# M503A.net
KiCad netlist of a schematic drawn in EAGLE
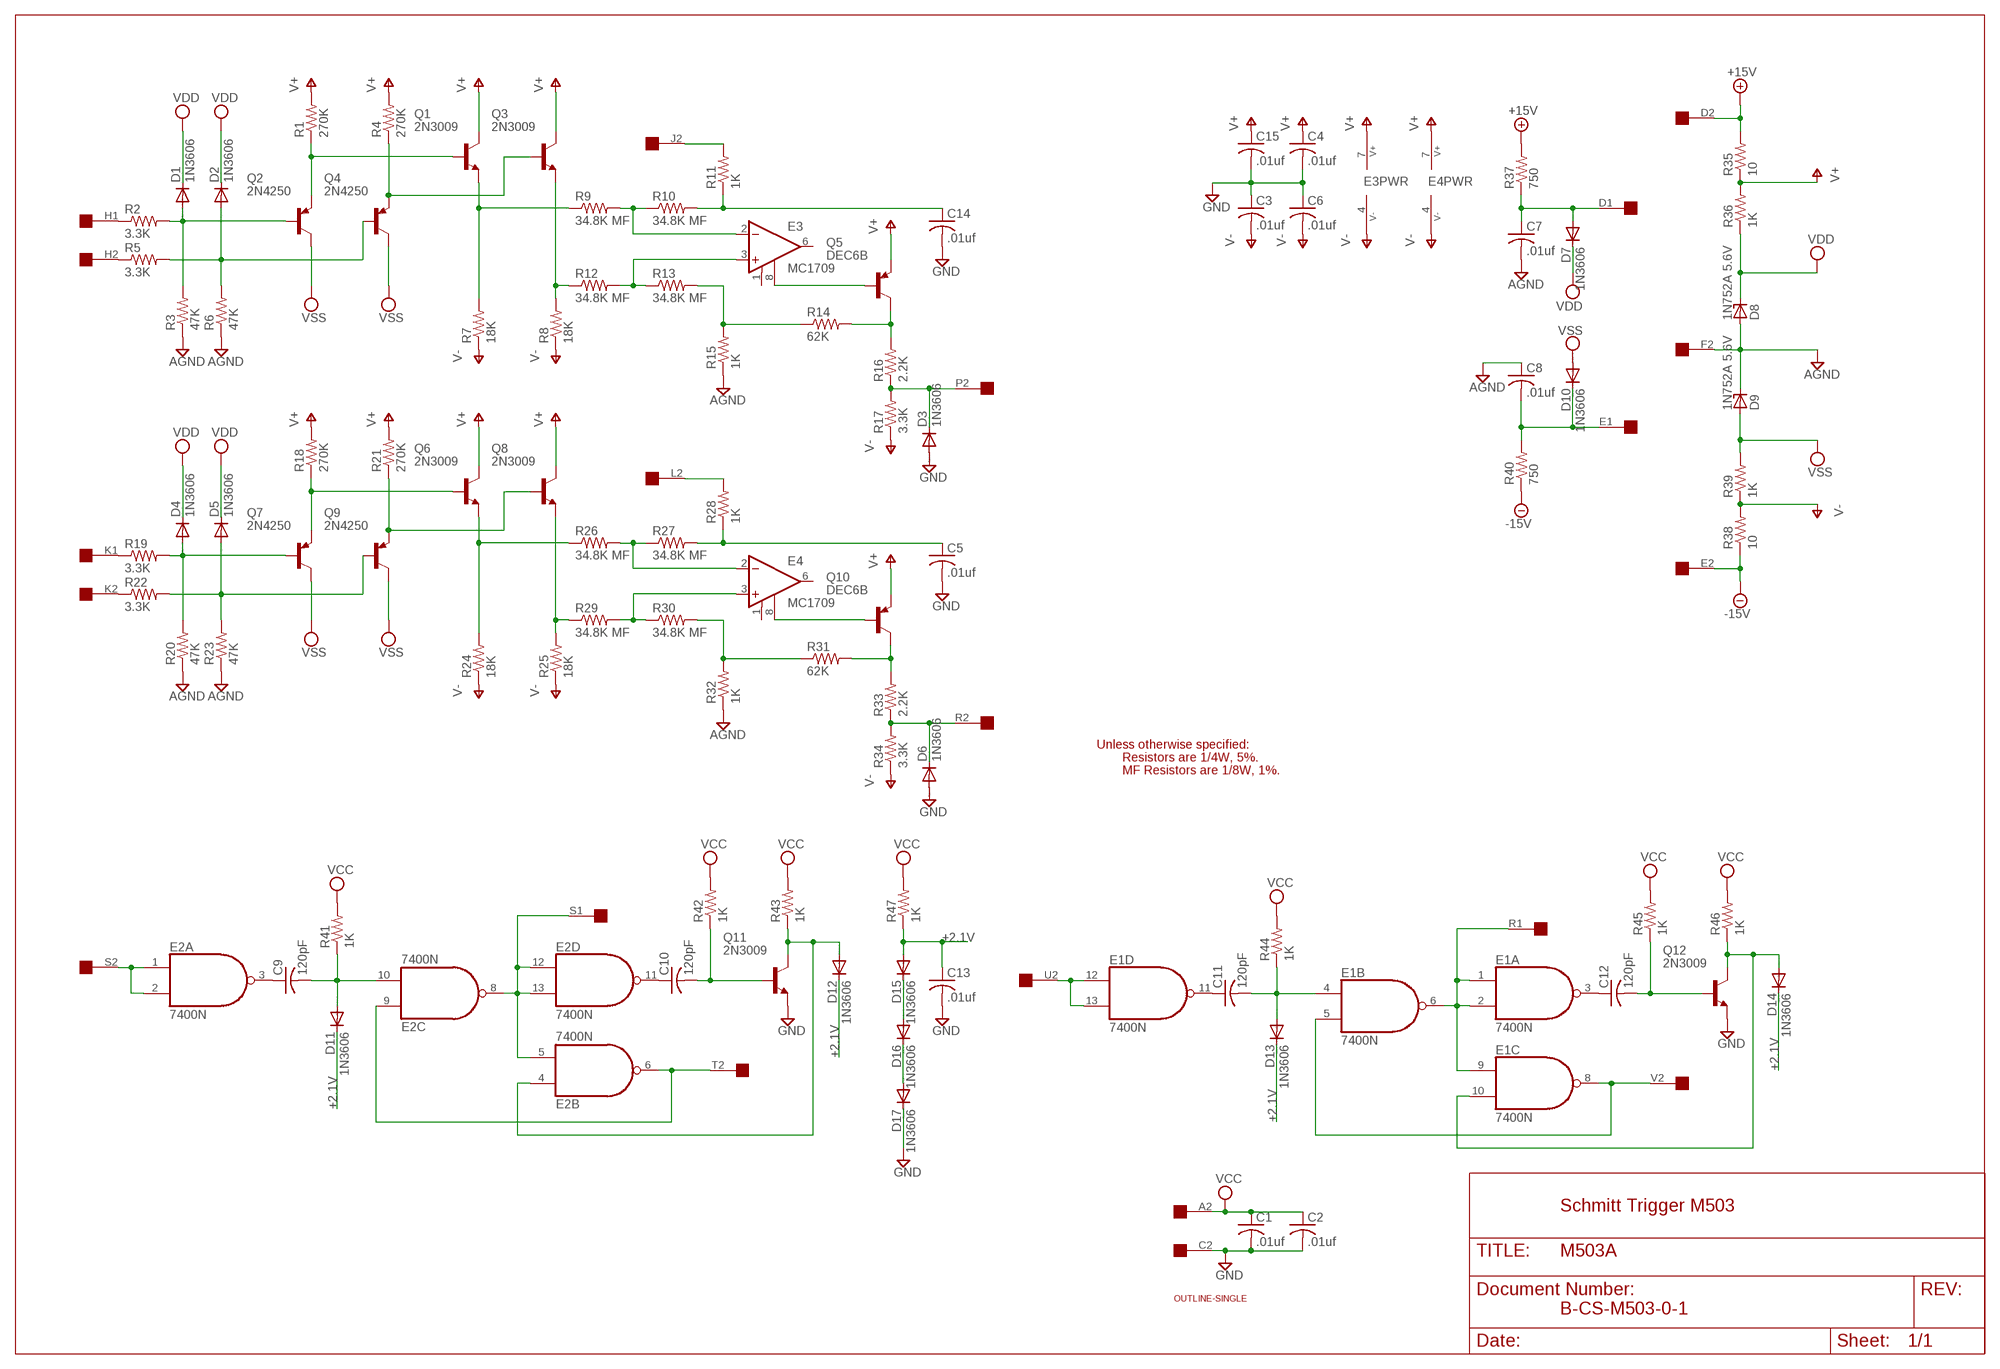
[diagram p0: schematic, sheet 1]

(export (version "E")
  (design (tool "Eeschema 10.0.6"))
  (components
    (comp (ref "C1")
      (value ".01uf")
      (footprint "eagle-import:C075-032X103")
      (libsource (lib "eagle-import") (part "C-US075-032X103"))
    )
    (comp (ref "C2")
      (value ".01uf")
      (footprint "eagle-import:C075-032X103")
      (libsource (lib "eagle-import") (part "C-US075-032X103"))
    )
    (comp (ref "C3")
      (value ".01uf")
      (footprint "eagle-import:C050-025X075")
      (libsource (lib "eagle-import") (part "C-US050-025X075"))
    )
    (comp (ref "C4")
      (value ".01uf")
      (footprint "eagle-import:C050-025X075")
      (libsource (lib "eagle-import") (part "C-US050-025X075"))
    )
    (comp (ref "C5")
      (value ".01uf")
      (footprint "eagle-import:C050-025X075")
      (libsource (lib "eagle-import") (part "C-US050-025X075"))
    )
    (comp (ref "C6")
      (value ".01uf")
      (footprint "eagle-import:C050-025X075")
      (libsource (lib "eagle-import") (part "C-US050-025X075"))
    )
    (comp (ref "C7")
      (value ".01uf")
      (footprint "eagle-import:C050-025X075")
      (libsource (lib "eagle-import") (part "C-US050-025X075"))
    )
    (comp (ref "C8")
      (value ".01uf")
      (footprint "eagle-import:C050-025X075")
      (libsource (lib "eagle-import") (part "C-US050-025X075"))
    )
    (comp (ref "C9")
      (value "120pF")
      (footprint "eagle-import:C050-025X075")
      (libsource (lib "eagle-import") (part "C-US050-025X075"))
    )
    (comp (ref "C10")
      (value "120pF")
      (footprint "eagle-import:C050-025X075")
      (libsource (lib "eagle-import") (part "C-US050-025X075"))
    )
    (comp (ref "C11")
      (value "120pF")
      (footprint "eagle-import:C050-025X075")
      (libsource (lib "eagle-import") (part "C-US050-025X075"))
    )
    (comp (ref "C12")
      (value "120pF")
      (footprint "eagle-import:C050-025X075")
      (libsource (lib "eagle-import") (part "C-US050-025X075"))
    )
    (comp (ref "C13")
      (value ".01uf")
      (footprint "eagle-import:C050-025X075")
      (libsource (lib "eagle-import") (part "C-US050-025X075"))
    )
    (comp (ref "C14")
      (value ".01uf")
      (footprint "eagle-import:C050-025X075")
      (libsource (lib "eagle-import") (part "C-US050-025X075"))
    )
    (comp (ref "C15")
      (value ".01uf")
      (footprint "eagle-import:C050-025X075")
      (libsource (lib "eagle-import") (part "C-US050-025X075"))
    )
    (comp (ref "D1")
      (value "1N3606")
      (footprint "eagle-import:DO35-10")
      (libsource (lib "eagle-import") (part "1N4148DO35-10"))
    )
    (comp (ref "D2")
      (value "1N3606")
      (footprint "eagle-import:DO35-10")
      (libsource (lib "eagle-import") (part "1N4148DO35-10"))
    )
    (comp (ref "D3")
      (value "1N3606")
      (footprint "eagle-import:DO35-10")
      (libsource (lib "eagle-import") (part "1N4148DO35-10"))
    )
    (comp (ref "D4")
      (value "1N3606")
      (footprint "eagle-import:DO35-10")
      (libsource (lib "eagle-import") (part "1N4148DO35-10"))
    )
    (comp (ref "D5")
      (value "1N3606")
      (footprint "eagle-import:DO35-10")
      (libsource (lib "eagle-import") (part "1N4148DO35-10"))
    )
    (comp (ref "D6")
      (value "1N3606")
      (footprint "eagle-import:DO35-10")
      (libsource (lib "eagle-import") (part "1N4148DO35-10"))
    )
    (comp (ref "D7")
      (value "1N3606")
      (footprint "eagle-import:DO35-10")
      (libsource (lib "eagle-import") (part "1N4148DO35-10"))
    )
    (comp (ref "D8")
      (value "1N752A 5.6V")
      (footprint "eagle-import:DO35Z10")
      (libsource (lib "eagle-import") (part "ZENER-DIODEDO35Z10"))
    )
    (comp (ref "D9")
      (value "1N752A 5.6V")
      (footprint "eagle-import:DO35Z10")
      (libsource (lib "eagle-import") (part "ZENER-DIODEDO35Z10"))
    )
    (comp (ref "D10")
      (value "1N3606")
      (footprint "eagle-import:DO35-10")
      (libsource (lib "eagle-import") (part "1N4148DO35-10"))
    )
    (comp (ref "D11")
      (value "1N3606")
      (footprint "eagle-import:DO35-10")
      (libsource (lib "eagle-import") (part "1N4148DO35-10"))
    )
    (comp (ref "D12")
      (value "1N3606")
      (footprint "eagle-import:DO35-10")
      (libsource (lib "eagle-import") (part "1N4148DO35-10"))
    )
    (comp (ref "D13")
      (value "1N3606")
      (footprint "eagle-import:DO35-10")
      (libsource (lib "eagle-import") (part "1N4148DO35-10"))
    )
    (comp (ref "D14")
      (value "1N3606")
      (footprint "eagle-import:DO35-10")
      (libsource (lib "eagle-import") (part "1N4148DO35-10"))
    )
    (comp (ref "D15")
      (value "1N3606")
      (footprint "eagle-import:DO35-10")
      (libsource (lib "eagle-import") (part "1N4148DO35-10"))
    )
    (comp (ref "D16")
      (value "1N3606")
      (footprint "eagle-import:DO35-10")
      (libsource (lib "eagle-import") (part "1N4148DO35-10"))
    )
    (comp (ref "D17")
      (value "1N3606")
      (footprint "eagle-import:DO35-10")
      (libsource (lib "eagle-import") (part "1N4148DO35-10"))
    )
    (comp (ref "E1")
      (value "7400N")
      (footprint "eagle-import:DIL14")
      (libsource (lib "eagle-import") (part "7400N"))
    )
    (comp (ref "E2")
      (value "7400N")
      (footprint "eagle-import:DIL14")
      (libsource (lib "eagle-import") (part "7400N"))
    )
    (comp (ref "E3")
      (value "MC1709")
      (footprint "eagle-import:TO99C")
      (libsource (lib "eagle-import") (part "LM301C"))
    )
    (comp (ref "E4")
      (value "MC1709")
      (footprint "eagle-import:TO99B")
      (libsource (lib "eagle-import") (part "LM301B"))
    )
    (comp (ref "Q1")
      (value "2N3009")
      (footprint "eagle-import:TO39")
      (libsource (lib "eagle-import") (part "2N3019"))
    )
    (comp (ref "Q2")
      (value "2N4250")
      (footprint "eagle-import:TO39")
      (libsource (lib "eagle-import") (part "2N2904"))
    )
    (comp (ref "Q3")
      (value "2N3009")
      (footprint "eagle-import:TO39")
      (libsource (lib "eagle-import") (part "2N3019"))
    )
    (comp (ref "Q4")
      (value "2N4250")
      (footprint "eagle-import:TO39")
      (libsource (lib "eagle-import") (part "2N2904"))
    )
    (comp (ref "Q5")
      (value "DEC6B")
      (footprint "eagle-import:TO39")
      (libsource (lib "eagle-import") (part "2N2904"))
    )
    (comp (ref "Q6")
      (value "2N3009")
      (footprint "eagle-import:TO39")
      (libsource (lib "eagle-import") (part "2N3019"))
    )
    (comp (ref "Q7")
      (value "2N4250")
      (footprint "eagle-import:TO39")
      (libsource (lib "eagle-import") (part "2N2904"))
    )
    (comp (ref "Q8")
      (value "2N3009")
      (footprint "eagle-import:TO39")
      (libsource (lib "eagle-import") (part "2N3019"))
    )
    (comp (ref "Q9")
      (value "2N4250")
      (footprint "eagle-import:TO39")
      (libsource (lib "eagle-import") (part "2N2904"))
    )
    (comp (ref "Q10")
      (value "DEC6B")
      (footprint "eagle-import:TO39")
      (libsource (lib "eagle-import") (part "2N2904"))
    )
    (comp (ref "Q11")
      (value "2N3009")
      (footprint "eagle-import:TO39")
      (libsource (lib "eagle-import") (part "2N3019"))
    )
    (comp (ref "Q12")
      (value "2N3009")
      (footprint "eagle-import:TO39")
      (libsource (lib "eagle-import") (part "2N3019"))
    )
    (comp (ref "R1")
      (value "270K")
      (footprint "eagle-import:0207_10")
      (libsource (lib "eagle-import") (part "R-US_0207/10"))
    )
    (comp (ref "R2")
      (value "3.3K")
      (footprint "eagle-import:0207_10")
      (libsource (lib "eagle-import") (part "R-US_0207/10"))
    )
    (comp (ref "R3")
      (value "47K")
      (footprint "eagle-import:0207_10")
      (libsource (lib "eagle-import") (part "R-US_0207/10"))
    )
    (comp (ref "R4")
      (value "270K")
      (footprint "eagle-import:0207_10")
      (libsource (lib "eagle-import") (part "R-US_0207/10"))
    )
    (comp (ref "R5")
      (value "3.3K")
      (footprint "eagle-import:0207_10")
      (libsource (lib "eagle-import") (part "R-US_0207/10"))
    )
    (comp (ref "R6")
      (value "47K")
      (footprint "eagle-import:0207_10")
      (libsource (lib "eagle-import") (part "R-US_0207/10"))
    )
    (comp (ref "R7")
      (value "18K")
      (footprint "eagle-import:0207_10")
      (libsource (lib "eagle-import") (part "R-US_0207/10"))
    )
    (comp (ref "R8")
      (value "18K")
      (footprint "eagle-import:0207_10")
      (libsource (lib "eagle-import") (part "R-US_0207/10"))
    )
    (comp (ref "R9")
      (value "34.8K MF")
      (footprint "eagle-import:0207_10")
      (libsource (lib "eagle-import") (part "R-US_0207/10"))
    )
    (comp (ref "R10")
      (value "34.8K MF")
      (footprint "eagle-import:0207_10")
      (libsource (lib "eagle-import") (part "R-US_0207/10"))
    )
    (comp (ref "R11")
      (value "1K")
      (footprint "eagle-import:0207_10")
      (libsource (lib "eagle-import") (part "R-US_0207/10"))
    )
    (comp (ref "R12")
      (value "34.8K MF")
      (footprint "eagle-import:0207_10")
      (libsource (lib "eagle-import") (part "R-US_0207/10"))
    )
    (comp (ref "R13")
      (value "34.8K MF")
      (footprint "eagle-import:0207_10")
      (libsource (lib "eagle-import") (part "R-US_0207/10"))
    )
    (comp (ref "R14")
      (value "62K")
      (footprint "eagle-import:0207_10")
      (libsource (lib "eagle-import") (part "R-US_0207/10"))
    )
    (comp (ref "R15")
      (value "1K")
      (footprint "eagle-import:0207_10")
      (libsource (lib "eagle-import") (part "R-US_0207/10"))
    )
    (comp (ref "R16")
      (value "2.2K")
      (footprint "eagle-import:0207_10")
      (libsource (lib "eagle-import") (part "R-US_0207/10"))
    )
    (comp (ref "R17")
      (value "3.3K")
      (footprint "eagle-import:0207_10")
      (libsource (lib "eagle-import") (part "R-US_0207/10"))
    )
    (comp (ref "R18")
      (value "270K")
      (footprint "eagle-import:0207_10")
      (libsource (lib "eagle-import") (part "R-US_0207/10"))
    )
    (comp (ref "R19")
      (value "3.3K")
      (footprint "eagle-import:0207_10")
      (libsource (lib "eagle-import") (part "R-US_0207/10"))
    )
    (comp (ref "R20")
      (value "47K")
      (footprint "eagle-import:0207_10")
      (libsource (lib "eagle-import") (part "R-US_0207/10"))
    )
    (comp (ref "R21")
      (value "270K")
      (footprint "eagle-import:0207_10")
      (libsource (lib "eagle-import") (part "R-US_0207/10"))
    )
    (comp (ref "R22")
      (value "3.3K")
      (footprint "eagle-import:0207_10")
      (libsource (lib "eagle-import") (part "R-US_0207/10"))
    )
    (comp (ref "R23")
      (value "47K")
      (footprint "eagle-import:0207_10")
      (libsource (lib "eagle-import") (part "R-US_0207/10"))
    )
    (comp (ref "R24")
      (value "18K")
      (footprint "eagle-import:0207_10")
      (libsource (lib "eagle-import") (part "R-US_0207/10"))
    )
    (comp (ref "R25")
      (value "18K")
      (footprint "eagle-import:0207_10")
      (libsource (lib "eagle-import") (part "R-US_0207/10"))
    )
    (comp (ref "R26")
      (value "34.8K MF")
      (footprint "eagle-import:0207_10")
      (libsource (lib "eagle-import") (part "R-US_0207/10"))
    )
    (comp (ref "R27")
      (value "34.8K MF")
      (footprint "eagle-import:0207_10")
      (libsource (lib "eagle-import") (part "R-US_0207/10"))
    )
    (comp (ref "R28")
      (value "1K")
      (footprint "eagle-import:0207_10")
      (libsource (lib "eagle-import") (part "R-US_0207/10"))
    )
    (comp (ref "R29")
      (value "34.8K MF")
      (footprint "eagle-import:0207_10")
      (libsource (lib "eagle-import") (part "R-US_0207/10"))
    )
    (comp (ref "R30")
      (value "34.8K MF")
      (footprint "eagle-import:0207_10")
      (libsource (lib "eagle-import") (part "R-US_0207/10"))
    )
    (comp (ref "R31")
      (value "62K")
      (footprint "eagle-import:0207_10")
      (libsource (lib "eagle-import") (part "R-US_0207/10"))
    )
    (comp (ref "R32")
      (value "1K")
      (footprint "eagle-import:0207_10")
      (libsource (lib "eagle-import") (part "R-US_0207/10"))
    )
    (comp (ref "R33")
      (value "2.2K")
      (footprint "eagle-import:0207_10")
      (libsource (lib "eagle-import") (part "R-US_0207/10"))
    )
    (comp (ref "R34")
      (value "3.3K")
      (footprint "eagle-import:0207_10")
      (libsource (lib "eagle-import") (part "R-US_0207/10"))
    )
    (comp (ref "R35")
      (value "10")
      (footprint "eagle-import:0207_10")
      (libsource (lib "eagle-import") (part "R-US_0207/10"))
    )
    (comp (ref "R36")
      (value "1K")
      (footprint "eagle-import:0207_10")
      (libsource (lib "eagle-import") (part "R-US_0207/10"))
    )
    (comp (ref "R37")
      (value "750")
      (footprint "eagle-import:0207_10")
      (libsource (lib "eagle-import") (part "R-US_0207/10"))
    )
    (comp (ref "R38")
      (value "10")
      (footprint "eagle-import:0207_10")
      (libsource (lib "eagle-import") (part "R-US_0207/10"))
    )
    (comp (ref "R39")
      (value "1K")
      (footprint "eagle-import:0207_10")
      (libsource (lib "eagle-import") (part "R-US_0207/10"))
    )
    (comp (ref "R40")
      (value "750")
      (footprint "eagle-import:0207_10")
      (libsource (lib "eagle-import") (part "R-US_0207/10"))
    )
    (comp (ref "R41")
      (value "1K")
      (footprint "eagle-import:0207_10")
      (libsource (lib "eagle-import") (part "R-US_0207/10"))
    )
    (comp (ref "R42")
      (value "1K")
      (footprint "eagle-import:0207_10")
      (libsource (lib "eagle-import") (part "R-US_0207/10"))
    )
    (comp (ref "R43")
      (value "1K")
      (footprint "eagle-import:0207_10")
      (libsource (lib "eagle-import") (part "R-US_0207/10"))
    )
    (comp (ref "R44")
      (value "1K")
      (footprint "eagle-import:0207_10")
      (libsource (lib "eagle-import") (part "R-US_0207/10"))
    )
    (comp (ref "R45")
      (value "1K")
      (footprint "eagle-import:0207_10")
      (libsource (lib "eagle-import") (part "R-US_0207/10"))
    )
    (comp (ref "R46")
      (value "1K")
      (footprint "eagle-import:0207_10")
      (libsource (lib "eagle-import") (part "R-US_0207/10"))
    )
    (comp (ref "R47")
      (value "1K")
      (footprint "eagle-import:0207_10")
      (libsource (lib "eagle-import") (part "R-US_0207/10"))
    )
    (comp (ref "U$2")
      (value "SINGLE")
      (footprint "eagle-import:EDGE-CON2")
      (libsource (lib "eagle-import") (part "SINGLE"))
    )
    (comp (ref "U$4")
      (value "OUTLINE-SINGLE")
      (footprint "eagle-import:SINGLE")
      (libsource (lib "eagle-import") (part "OUTLINE-SINGLE"))
    )
  )
  (nets
    (net (code "1") (name "+15V") (class "Default")
      (node (ref "R35") (pin "2") (pinfunction "2_2") (pintype "passive"))
      (node (ref "R37") (pin "2") (pinfunction "2_2") (pintype "passive"))
      (node (ref "U$2") (pin "D2") (pinfunction "1_D2") (pintype "bidirectional"))
    )
    (net (code "2") (name "-15V") (class "Default")
      (node (ref "R38") (pin "1") (pinfunction "1_1") (pintype "passive"))
      (node (ref "R40") (pin "1") (pinfunction "1_1") (pintype "passive"))
      (node (ref "U$2") (pin "E2") (pinfunction "1_E2") (pintype "bidirectional"))
    )
    (net (code "3") (name "/+2.1V") (class "Default")
      (node (ref "C13") (pin "1") (pinfunction "1_1") (pintype "passive"))
      (node (ref "D11") (pin "C") (pinfunction "C_C") (pintype "passive"))
      (node (ref "D12") (pin "C") (pinfunction "C_C") (pintype "passive"))
      (node (ref "D13") (pin "C") (pinfunction "C_C") (pintype "passive"))
      (node (ref "D14") (pin "C") (pinfunction "C_C") (pintype "passive"))
      (node (ref "D15") (pin "A") (pinfunction "A_A") (pintype "passive"))
      (node (ref "R47") (pin "1") (pinfunction "1_1") (pintype "passive"))
    )
    (net (code "4") (name "AGND") (class "Default")
      (node (ref "C7") (pin "2") (pinfunction "2_2") (pintype "passive"))
      (node (ref "C8") (pin "1") (pinfunction "1_1") (pintype "passive"))
      (node (ref "D8") (pin "A") (pinfunction "A_A") (pintype "passive"))
      (node (ref "D9") (pin "C") (pinfunction "C_C") (pintype "passive"))
      (node (ref "R15") (pin "1") (pinfunction "1_1") (pintype "passive"))
      (node (ref "R20") (pin "1") (pinfunction "1_1") (pintype "passive"))
      (node (ref "R23") (pin "1") (pinfunction "1_1") (pintype "passive"))
      (node (ref "R3") (pin "1") (pinfunction "1_1") (pintype "passive"))
      (node (ref "R32") (pin "1") (pinfunction "1_1") (pintype "passive"))
      (node (ref "R6") (pin "1") (pinfunction "1_1") (pintype "passive"))
      (node (ref "U$2") (pin "F2") (pinfunction "1_F2") (pintype "bidirectional"))
    )
    (net (code "5") (name "GND") (class "Default")
      (node (ref "C1") (pin "2") (pinfunction "2_2") (pintype "passive"))
      (node (ref "C13") (pin "2") (pinfunction "2_2") (pintype "passive"))
      (node (ref "C14") (pin "2") (pinfunction "2_2") (pintype "passive"))
      (node (ref "C15") (pin "2") (pinfunction "2_2") (pintype "passive"))
      (node (ref "C2") (pin "2") (pinfunction "2_2") (pintype "passive"))
      (node (ref "C3") (pin "1") (pinfunction "1_1") (pintype "passive"))
      (node (ref "C4") (pin "2") (pinfunction "2_2") (pintype "passive"))
      (node (ref "C5") (pin "2") (pinfunction "2_2") (pintype "passive"))
      (node (ref "C6") (pin "1") (pinfunction "1_1") (pintype "passive"))
      (node (ref "D17") (pin "C") (pinfunction "C_C") (pintype "passive"))
      (node (ref "D3") (pin "A") (pinfunction "A_A") (pintype "passive"))
      (node (ref "D6") (pin "A") (pinfunction "A_A") (pintype "passive"))
      (node (ref "Q11") (pin "1") (pinfunction "E_1") (pintype "passive"))
      (node (ref "Q12") (pin "1") (pinfunction "E_1") (pintype "passive"))
      (node (ref "U$2") (pin "C2") (pinfunction "1_C2") (pintype "bidirectional"))
    )
    (net (code "6") (name "Net-(C5-Pad1)") (class "Default")
      (node (ref "C5") (pin "1") (pinfunction "1_1") (pintype "passive"))
      (node (ref "R27") (pin "2") (pinfunction "2_2") (pintype "passive"))
      (node (ref "R28") (pin "1") (pinfunction "1_1") (pintype "passive"))
    )
    (net (code "7") (name "Net-(C14-Pad1)") (class "Default")
      (node (ref "C14") (pin "1") (pinfunction "1_1") (pintype "passive"))
      (node (ref "R10") (pin "2") (pinfunction "2_2") (pintype "passive"))
      (node (ref "R11") (pin "1") (pinfunction "1_1") (pintype "passive"))
    )
    (net (code "8") (name "Net-(D15-PadC)") (class "Default")
      (node (ref "D15") (pin "C") (pinfunction "C_C") (pintype "passive"))
      (node (ref "D16") (pin "A") (pinfunction "A_A") (pintype "passive"))
    )
    (net (code "9") (name "Net-(D16-PadC)") (class "Default")
      (node (ref "D16") (pin "C") (pinfunction "C_C") (pintype "passive"))
      (node (ref "D17") (pin "A") (pinfunction "A_A") (pintype "passive"))
    )
    (net (code "10") (name "Net-(E1A-I0)") (class "Default")
      (node (ref "E1") (pin "1") (pinfunction "I0_1") (pintype "input"))
      (node (ref "E1") (pin "2") (pinfunction "I1_2") (pintype "input"))
      (node (ref "E1") (pin "6") (pinfunction "O_6") (pintype "output"))
      (node (ref "E1") (pin "9") (pinfunction "I0_9") (pintype "input"))
      (node (ref "U$2") (pin "R1") (pinfunction "1_R1") (pintype "bidirectional"))
    )
    (net (code "11") (name "Net-(E1A-O)") (class "Default")
      (node (ref "C12") (pin "1") (pinfunction "1_1") (pintype "passive"))
      (node (ref "E1") (pin "3") (pinfunction "O_3") (pintype "output"))
    )
    (net (code "12") (name "Net-(E1B-I0)") (class "Default")
      (node (ref "C11") (pin "2") (pinfunction "2_2") (pintype "passive"))
      (node (ref "D13") (pin "A") (pinfunction "A_A") (pintype "passive"))
      (node (ref "E1") (pin "4") (pinfunction "I0_4") (pintype "input"))
      (node (ref "R44") (pin "1") (pinfunction "1_1") (pintype "passive"))
    )
    (net (code "13") (name "Net-(E1B-I1)") (class "Default")
      (node (ref "E1") (pin "5") (pinfunction "I1_5") (pintype "input"))
      (node (ref "E1") (pin "8") (pinfunction "O_8") (pintype "output"))
      (node (ref "U$2") (pin "V2") (pinfunction "1_V2") (pintype "bidirectional"))
    )
    (net (code "14") (name "Net-(E1C-I1)") (class "Default")
      (node (ref "D14") (pin "A") (pinfunction "A_A") (pintype "passive"))
      (node (ref "E1") (pin "10") (pinfunction "I1_10") (pintype "input"))
      (node (ref "Q12") (pin "3") (pinfunction "C_3") (pintype "passive"))
      (node (ref "R46") (pin "1") (pinfunction "1_1") (pintype "passive"))
    )
    (net (code "15") (name "Net-(E1D-I0)") (class "Default")
      (node (ref "E1") (pin "12") (pinfunction "I0_12") (pintype "input"))
      (node (ref "E1") (pin "13") (pinfunction "I1_13") (pintype "input"))
      (node (ref "U$2") (pin "U2") (pinfunction "1_U2") (pintype "bidirectional"))
    )
    (net (code "16") (name "Net-(E1D-O)") (class "Default")
      (node (ref "C11") (pin "1") (pinfunction "1_1") (pintype "passive"))
      (node (ref "E1") (pin "11") (pinfunction "O_11") (pintype "output"))
    )
    (net (code "17") (name "Net-(E2A-I0)") (class "Default")
      (node (ref "E2") (pin "1") (pinfunction "I0_1") (pintype "input"))
      (node (ref "E2") (pin "2") (pinfunction "I1_2") (pintype "input"))
      (node (ref "U$2") (pin "S2") (pinfunction "1_S2") (pintype "bidirectional"))
    )
    (net (code "18") (name "Net-(E2A-O)") (class "Default")
      (node (ref "C9") (pin "1") (pinfunction "1_1") (pintype "passive"))
      (node (ref "E2") (pin "3") (pinfunction "O_3") (pintype "output"))
    )
    (net (code "19") (name "Net-(E2B-I0)") (class "Default")
      (node (ref "D12") (pin "A") (pinfunction "A_A") (pintype "passive"))
      (node (ref "E2") (pin "4") (pinfunction "I0_4") (pintype "input"))
      (node (ref "Q11") (pin "3") (pinfunction "C_3") (pintype "passive"))
      (node (ref "R43") (pin "1") (pinfunction "1_1") (pintype "passive"))
    )
    (net (code "20") (name "Net-(E2B-I1)") (class "Default")
      (node (ref "E2") (pin "12") (pinfunction "I0_12") (pintype "input"))
      (node (ref "E2") (pin "13") (pinfunction "I1_13") (pintype "input"))
      (node (ref "E2") (pin "5") (pinfunction "I1_5") (pintype "input"))
      (node (ref "E2") (pin "8") (pinfunction "O_8") (pintype "output"))
      (node (ref "U$2") (pin "S1") (pinfunction "1_S1") (pintype "bidirectional"))
    )
    (net (code "21") (name "Net-(E2B-O)") (class "Default")
      (node (ref "E2") (pin "6") (pinfunction "O_6") (pintype "output"))
      (node (ref "E2") (pin "9") (pinfunction "I0_9") (pintype "input"))
      (node (ref "U$2") (pin "T2") (pinfunction "1_T2") (pintype "bidirectional"))
    )
    (net (code "22") (name "Net-(E2C-I1)") (class "Default")
      (node (ref "C9") (pin "2") (pinfunction "2_2") (pintype "passive"))
      (node (ref "D11") (pin "A") (pinfunction "A_A") (pintype "passive"))
      (node (ref "E2") (pin "10") (pinfunction "I1_10") (pintype "input"))
      (node (ref "R41") (pin "1") (pinfunction "1_1") (pintype "passive"))
    )
    (net (code "23") (name "Net-(E2D-O)") (class "Default")
      (node (ref "C10") (pin "1") (pinfunction "1_1") (pintype "passive"))
      (node (ref "E2") (pin "11") (pinfunction "O_11") (pintype "output"))
    )
    (net (code "24") (name "Net-(E3A-+IN)") (class "Default")
      (node (ref "E3") (pin "3") (pinfunction "+IN_3") (pintype "input"))
      (node (ref "R12") (pin "2") (pinfunction "2_2") (pintype "passive"))
      (node (ref "R13") (pin "1") (pinfunction "1_1") (pintype "passive"))
    )
    (net (code "25") (name "Net-(E3A--IN)") (class "Default")
      (node (ref "E3") (pin "2") (pinfunction "-IN_2") (pintype "input"))
      (node (ref "R10") (pin "1") (pinfunction "1_1") (pintype "passive"))
      (node (ref "R9") (pin "2") (pinfunction "2_2") (pintype "passive"))
    )
    (net (code "26") (name "Net-(E3A-CMP)") (class "Default")
      (node (ref "E3") (pin "8") (pinfunction "CMP_8") (pintype "passive"))
      (node (ref "Q5") (pin "2") (pinfunction "B_2") (pintype "passive"))
    )
    (net (code "27") (name "Net-(E4A-+IN)") (class "Default")
      (node (ref "E4") (pin "3") (pinfunction "+IN_3") (pintype "input"))
      (node (ref "R29") (pin "2") (pinfunction "2_2") (pintype "passive"))
      (node (ref "R30") (pin "1") (pinfunction "1_1") (pintype "passive"))
    )
    (net (code "28") (name "Net-(E4A--IN)") (class "Default")
      (node (ref "E4") (pin "2") (pinfunction "-IN_2") (pintype "input"))
      (node (ref "R26") (pin "2") (pinfunction "2_2") (pintype "passive"))
      (node (ref "R27") (pin "1") (pinfunction "1_1") (pintype "passive"))
    )
    (net (code "29") (name "Net-(E4A-CMP)") (class "Default")
      (node (ref "E4") (pin "8") (pinfunction "CMP_8") (pintype "passive"))
      (node (ref "Q10") (pin "2") (pinfunction "B_2") (pintype "passive"))
    )
    (net (code "30") (name "Net-(Q1-B)") (class "Default")
      (node (ref "Q1") (pin "2") (pinfunction "B_2") (pintype "passive"))
      (node (ref "Q2") (pin "1") (pinfunction "E_1") (pintype "passive"))
      (node (ref "R1") (pin "1") (pinfunction "1_1") (pintype "passive"))
    )
    (net (code "31") (name "Net-(Q1-E)") (class "Default")
      (node (ref "Q1") (pin "1") (pinfunction "E_1") (pintype "passive"))
      (node (ref "R7") (pin "2") (pinfunction "2_2") (pintype "passive"))
      (node (ref "R9") (pin "1") (pinfunction "1_1") (pintype "passive"))
    )
    (net (code "32") (name "Net-(Q2-B)") (class "Default")
      (node (ref "D1") (pin "A") (pinfunction "A_A") (pintype "passive"))
      (node (ref "Q2") (pin "2") (pinfunction "B_2") (pintype "passive"))
      (node (ref "R2") (pin "2") (pinfunction "2_2") (pintype "passive"))
      (node (ref "R3") (pin "2") (pinfunction "2_2") (pintype "passive"))
    )
    (net (code "33") (name "Net-(Q3-B)") (class "Default")
      (node (ref "Q3") (pin "2") (pinfunction "B_2") (pintype "passive"))
      (node (ref "Q4") (pin "1") (pinfunction "E_1") (pintype "passive"))
      (node (ref "R4") (pin "1") (pinfunction "1_1") (pintype "passive"))
    )
    (net (code "34") (name "Net-(Q3-E)") (class "Default")
      (node (ref "Q3") (pin "1") (pinfunction "E_1") (pintype "passive"))
      (node (ref "R12") (pin "1") (pinfunction "1_1") (pintype "passive"))
      (node (ref "R8") (pin "2") (pinfunction "2_2") (pintype "passive"))
    )
    (net (code "35") (name "Net-(Q4-B)") (class "Default")
      (node (ref "D2") (pin "A") (pinfunction "A_A") (pintype "passive"))
      (node (ref "Q4") (pin "2") (pinfunction "B_2") (pintype "passive"))
      (node (ref "R5") (pin "2") (pinfunction "2_2") (pintype "passive"))
      (node (ref "R6") (pin "2") (pinfunction "2_2") (pintype "passive"))
    )
    (net (code "36") (name "Net-(Q5-C)") (class "Default")
      (node (ref "Q5") (pin "3") (pinfunction "C_3") (pintype "passive"))
      (node (ref "R14") (pin "2") (pinfunction "2_2") (pintype "passive"))
      (node (ref "R16") (pin "2") (pinfunction "2_2") (pintype "passive"))
    )
    (net (code "37") (name "Net-(Q6-B)") (class "Default")
      (node (ref "Q6") (pin "2") (pinfunction "B_2") (pintype "passive"))
      (node (ref "Q7") (pin "1") (pinfunction "E_1") (pintype "passive"))
      (node (ref "R18") (pin "1") (pinfunction "1_1") (pintype "passive"))
    )
    (net (code "38") (name "Net-(Q6-E)") (class "Default")
      (node (ref "Q6") (pin "1") (pinfunction "E_1") (pintype "passive"))
      (node (ref "R24") (pin "2") (pinfunction "2_2") (pintype "passive"))
      (node (ref "R26") (pin "1") (pinfunction "1_1") (pintype "passive"))
    )
    (net (code "39") (name "Net-(Q7-B)") (class "Default")
      (node (ref "D4") (pin "A") (pinfunction "A_A") (pintype "passive"))
      (node (ref "Q7") (pin "2") (pinfunction "B_2") (pintype "passive"))
      (node (ref "R19") (pin "2") (pinfunction "2_2") (pintype "passive"))
      (node (ref "R20") (pin "2") (pinfunction "2_2") (pintype "passive"))
    )
    (net (code "40") (name "Net-(Q8-B)") (class "Default")
      (node (ref "Q8") (pin "2") (pinfunction "B_2") (pintype "passive"))
      (node (ref "Q9") (pin "1") (pinfunction "E_1") (pintype "passive"))
      (node (ref "R21") (pin "1") (pinfunction "1_1") (pintype "passive"))
    )
    (net (code "41") (name "Net-(Q8-E)") (class "Default")
      (node (ref "Q8") (pin "1") (pinfunction "E_1") (pintype "passive"))
      (node (ref "R25") (pin "2") (pinfunction "2_2") (pintype "passive"))
      (node (ref "R29") (pin "1") (pinfunction "1_1") (pintype "passive"))
    )
    (net (code "42") (name "Net-(Q9-B)") (class "Default")
      (node (ref "D5") (pin "A") (pinfunction "A_A") (pintype "passive"))
      (node (ref "Q9") (pin "2") (pinfunction "B_2") (pintype "passive"))
      (node (ref "R22") (pin "2") (pinfunction "2_2") (pintype "passive"))
      (node (ref "R23") (pin "2") (pinfunction "2_2") (pintype "passive"))
    )
    (net (code "43") (name "Net-(Q10-C)") (class "Default")
      (node (ref "Q10") (pin "3") (pinfunction "C_3") (pintype "passive"))
      (node (ref "R31") (pin "2") (pinfunction "2_2") (pintype "passive"))
      (node (ref "R33") (pin "2") (pinfunction "2_2") (pintype "passive"))
    )
    (net (code "44") (name "Net-(Q11-B)") (class "Default")
      (node (ref "C10") (pin "2") (pinfunction "2_2") (pintype "passive"))
      (node (ref "Q11") (pin "2") (pinfunction "B_2") (pintype "passive"))
      (node (ref "R42") (pin "1") (pinfunction "1_1") (pintype "passive"))
    )
    (net (code "45") (name "Net-(Q12-B)") (class "Default")
      (node (ref "C12") (pin "2") (pinfunction "2_2") (pintype "passive"))
      (node (ref "Q12") (pin "2") (pinfunction "B_2") (pintype "passive"))
      (node (ref "R45") (pin "1") (pinfunction "1_1") (pintype "passive"))
    )
    (net (code "46") (name "Net-(R13-Pad2)") (class "Default")
      (node (ref "R13") (pin "2") (pinfunction "2_2") (pintype "passive"))
      (node (ref "R14") (pin "1") (pinfunction "1_1") (pintype "passive"))
      (node (ref "R15") (pin "2") (pinfunction "2_2") (pintype "passive"))
    )
    (net (code "47") (name "Net-(R30-Pad2)") (class "Default")
      (node (ref "R30") (pin "2") (pinfunction "2_2") (pintype "passive"))
      (node (ref "R31") (pin "1") (pinfunction "1_1") (pintype "passive"))
      (node (ref "R32") (pin "2") (pinfunction "2_2") (pintype "passive"))
    )
    (net (code "48") (name "Net-(U$2AB-1)") (class "Default")
      (node (ref "D6") (pin "C") (pinfunction "C_C") (pintype "passive"))
      (node (ref "R33") (pin "1") (pinfunction "1_1") (pintype "passive"))
      (node (ref "R34") (pin "2") (pinfunction "2_2") (pintype "passive"))
      (node (ref "U$2") (pin "R2") (pinfunction "1_R2") (pintype "bidirectional"))
    )
    (net (code "49") (name "Net-(U$2G-1)") (class "Default")
      (node (ref "C7") (pin "1") (pinfunction "1_1") (pintype "passive"))
      (node (ref "D7") (pin "A") (pinfunction "A_A") (pintype "passive"))
      (node (ref "R37") (pin "1") (pinfunction "1_1") (pintype "passive"))
      (node (ref "U$2") (pin "D1") (pinfunction "1_D1") (pintype "bidirectional"))
    )
    (net (code "50") (name "Net-(U$2I-1)") (class "Default")
      (node (ref "C8") (pin "2") (pinfunction "2_2") (pintype "passive"))
      (node (ref "D10") (pin "C") (pinfunction "C_C") (pintype "passive"))
      (node (ref "R40") (pin "2") (pinfunction "2_2") (pintype "passive"))
      (node (ref "U$2") (pin "E1") (pinfunction "1_E1") (pintype "bidirectional"))
    )
    (net (code "51") (name "Net-(U$2M-1)") (class "Default")
      (node (ref "R2") (pin "1") (pinfunction "1_1") (pintype "passive"))
      (node (ref "U$2") (pin "H1") (pinfunction "1_H1") (pintype "bidirectional"))
    )
    (net (code "52") (name "Net-(U$2N-1)") (class "Default")
      (node (ref "R5") (pin "1") (pinfunction "1_1") (pintype "passive"))
      (node (ref "U$2") (pin "H2") (pinfunction "1_H2") (pintype "bidirectional"))
    )
    (net (code "53") (name "Net-(U$2P-1)") (class "Default")
      (node (ref "R11") (pin "2") (pinfunction "2_2") (pintype "passive"))
      (node (ref "U$2") (pin "J2") (pinfunction "1_J2") (pintype "bidirectional"))
    )
    (net (code "54") (name "Net-(U$2Q-1)") (class "Default")
      (node (ref "R19") (pin "1") (pinfunction "1_1") (pintype "passive"))
      (node (ref "U$2") (pin "K1") (pinfunction "1_K1") (pintype "bidirectional"))
    )
    (net (code "55") (name "Net-(U$2R-1)") (class "Default")
      (node (ref "R22") (pin "1") (pinfunction "1_1") (pintype "passive"))
      (node (ref "U$2") (pin "K2") (pinfunction "1_K2") (pintype "bidirectional"))
    )
    (net (code "56") (name "Net-(U$2T-1)") (class "Default")
      (node (ref "R28") (pin "2") (pinfunction "2_2") (pintype "passive"))
      (node (ref "U$2") (pin "L2") (pinfunction "1_L2") (pintype "bidirectional"))
    )
    (net (code "57") (name "Net-(U$2Z-1)") (class "Default")
      (node (ref "D3") (pin "C") (pinfunction "C_C") (pintype "passive"))
      (node (ref "R16") (pin "1") (pinfunction "1_1") (pintype "passive"))
      (node (ref "R17") (pin "2") (pinfunction "2_2") (pintype "passive"))
      (node (ref "U$2") (pin "P2") (pinfunction "1_P2") (pintype "bidirectional"))
    )
    (net (code "58") (name "V+") (class "Default")
      (node (ref "C15") (pin "1") (pinfunction "1_1") (pintype "passive"))
      (node (ref "C4") (pin "1") (pinfunction "1_1") (pintype "passive"))
      (node (ref "E3") (pin "7") (pinfunction "+10V_7") (pintype "power_in"))
      (node (ref "E4") (pin "7") (pinfunction "+10V_7") (pintype "power_in"))
      (node (ref "Q1") (pin "3") (pinfunction "C_3") (pintype "passive"))
      (node (ref "Q10") (pin "1") (pinfunction "E_1") (pintype "passive"))
      (node (ref "Q3") (pin "3") (pinfunction "C_3") (pintype "passive"))
      (node (ref "Q5") (pin "1") (pinfunction "E_1") (pintype "passive"))
      (node (ref "Q6") (pin "3") (pinfunction "C_3") (pintype "passive"))
      (node (ref "Q8") (pin "3") (pinfunction "C_3") (pintype "passive"))
      (node (ref "R1") (pin "2") (pinfunction "2_2") (pintype "passive"))
      (node (ref "R18") (pin "2") (pinfunction "2_2") (pintype "passive"))
      (node (ref "R21") (pin "2") (pinfunction "2_2") (pintype "passive"))
      (node (ref "R35") (pin "1") (pinfunction "1_1") (pintype "passive"))
      (node (ref "R36") (pin "2") (pinfunction "2_2") (pintype "passive"))
      (node (ref "R4") (pin "2") (pinfunction "2_2") (pintype "passive"))
    )
    (net (code "59") (name "V-") (class "Default")
      (node (ref "C3") (pin "2") (pinfunction "2_2") (pintype "passive"))
      (node (ref "C6") (pin "2") (pinfunction "2_2") (pintype "passive"))
      (node (ref "E3") (pin "4") (pinfunction "-15V_4") (pintype "power_in"))
      (node (ref "E4") (pin "4") (pinfunction "-15V_4") (pintype "power_in"))
      (node (ref "R17") (pin "1") (pinfunction "1_1") (pintype "passive"))
      (node (ref "R24") (pin "1") (pinfunction "1_1") (pintype "passive"))
      (node (ref "R25") (pin "1") (pinfunction "1_1") (pintype "passive"))
      (node (ref "R34") (pin "1") (pinfunction "1_1") (pintype "passive"))
      (node (ref "R38") (pin "2") (pinfunction "2_2") (pintype "passive"))
      (node (ref "R39") (pin "1") (pinfunction "1_1") (pintype "passive"))
      (node (ref "R7") (pin "1") (pinfunction "1_1") (pintype "passive"))
      (node (ref "R8") (pin "1") (pinfunction "1_1") (pintype "passive"))
    )
    (net (code "60") (name "VCC") (class "Default")
      (node (ref "C1") (pin "1") (pinfunction "1_1") (pintype "passive"))
      (node (ref "C2") (pin "1") (pinfunction "1_1") (pintype "passive"))
      (node (ref "R41") (pin "2") (pinfunction "2_2") (pintype "passive"))
      (node (ref "R42") (pin "2") (pinfunction "2_2") (pintype "passive"))
      (node (ref "R43") (pin "2") (pinfunction "2_2") (pintype "passive"))
      (node (ref "R44") (pin "2") (pinfunction "2_2") (pintype "passive"))
      (node (ref "R45") (pin "2") (pinfunction "2_2") (pintype "passive"))
      (node (ref "R46") (pin "2") (pinfunction "2_2") (pintype "passive"))
      (node (ref "R47") (pin "2") (pinfunction "2_2") (pintype "passive"))
      (node (ref "U$2") (pin "A2") (pinfunction "1_A2") (pintype "bidirectional"))
    )
    (net (code "61") (name "VDD") (class "Default")
      (node (ref "D1") (pin "C") (pinfunction "C_C") (pintype "passive"))
      (node (ref "D2") (pin "C") (pinfunction "C_C") (pintype "passive"))
      (node (ref "D4") (pin "C") (pinfunction "C_C") (pintype "passive"))
      (node (ref "D5") (pin "C") (pinfunction "C_C") (pintype "passive"))
      (node (ref "D7") (pin "C") (pinfunction "C_C") (pintype "passive"))
      (node (ref "D8") (pin "C") (pinfunction "C_C") (pintype "passive"))
      (node (ref "R36") (pin "1") (pinfunction "1_1") (pintype "passive"))
    )
    (net (code "62") (name "VSS") (class "Default")
      (node (ref "D10") (pin "A") (pinfunction "A_A") (pintype "passive"))
      (node (ref "D9") (pin "A") (pinfunction "A_A") (pintype "passive"))
      (node (ref "Q2") (pin "3") (pinfunction "C_3") (pintype "passive"))
      (node (ref "Q4") (pin "3") (pinfunction "C_3") (pintype "passive"))
      (node (ref "Q7") (pin "3") (pinfunction "C_3") (pintype "passive"))
      (node (ref "Q9") (pin "3") (pinfunction "C_3") (pintype "passive"))
      (node (ref "R39") (pin "2") (pinfunction "2_2") (pintype "passive"))
    )
    (net (code "63") (name "unconnected-(E3A-ON{slash}CMP-Pad1)") (class "Default")
      (node (ref "E3") (pin "1") (pinfunction "ON/CMP_1") (pintype "passive"))
    )
    (net (code "64") (name "unconnected-(E3A-OUT-Pad6)") (class "Default")
      (node (ref "E3") (pin "6") (pinfunction "OUT_6") (pintype "output"))
    )
    (net (code "65") (name "unconnected-(E4A-ON{slash}CMP-Pad1)") (class "Default")
      (node (ref "E4") (pin "1") (pinfunction "ON/CMP_1") (pintype "passive"))
    )
    (net (code "66") (name "unconnected-(E4A-OUT-Pad6)") (class "Default")
      (node (ref "E4") (pin "6") (pinfunction "OUT_6") (pintype "output"))
    )
  )
)
